# Eload_Gen_3_Power_Module_-_Input_Rev_2.net
KiCad netlist of a schematic drawn in Altium Designer
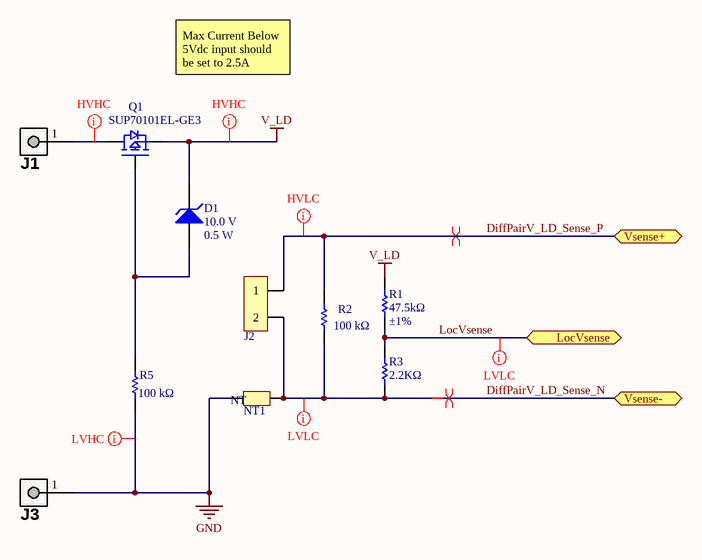
[diagram p0: Eload Gen 3 Power Module - Input Rev 2.SchDoc]

(export (version "E")
  (design (tool "Eeschema 10.0.6"))
  (components
    (comp (ref "D1")
      (value "MMSZ5240BT1G")
      (footprint "SOD123")
      (description "Zener Voltage Regulator, 500 mW, 2-Pin SOD-123, Pb-Free, Tape and Reel")
      (fields (field (name "BREAKDOWN VOLTAGE") "10.0 V") (field (name "POWER RATING") "0.5 W"))
      (libsource (lib "Master JULY2019") (part "Diode, Zener,SOD-123,10V,500mW, MMSZ5240BT1G"))
    )
    (comp (ref "J1")
      (value "wire teminal, lugs, screw, Keystone 8197")
      (footprint "Keystone 8197")
      (fields (field (name "MANUFACTURER PART NUMBER") "8197"))
      (libsource (lib "Master JULY2019") (part "wire teminal, lugs, screw, Keystone 8197"))
    )
    (comp (ref "J2")
      (value "TE Connectivity 282836-2")
      (footprint "TERM BLOCK 2POS SIDE ENTRY 5MM")
      (description "Wire to Board 2 Position 5 mm Pitch 30-16 AWG Euro Style Terminal Block")
      (fields (field (name "MANUFACTURER PART NUMBER") "282836-2"))
      (libsource (lib "Master JULY2019") (part "TERM BLOCK 2POS SIDE ENTRY 5MM, 282836-2"))
    )
    (comp (ref "J3")
      (value "wire teminal, lugs, screw, Keystone 8197")
      (footprint "Keystone 8197")
      (fields (field (name "MANUFACTURER PART NUMBER") "8197"))
      (libsource (lib "Master JULY2019") (part "wire teminal, lugs, screw, Keystone 8197"))
    )
    (comp (ref "NT1")
      (value "Net Tie,0.254mm")
      (footprint "0.254mm Net Tie")
      (libsource (lib "Master Mar2021") (part "Net Tie,0.254mm"))
    )
    (comp (ref "Q1")
      (value "SUP70101EL-GE3")
      (footprint "TO-220 RA")
      (description "MOSFET P-CH 100V 120A TO220AB")
      (fields (field (name "MANUFACTURER") "Vishay Siliconix"))
      (libsource (lib "Master JULY2019") (part "MOSFET,P-Chan,100V,120A,TO220, SUP70101EL-GE3"))
    )
    (comp (ref "R1")
      (value "RK73H2ATTD4752F")
      (footprint "res, 0805, HD")
      (fields
        (field (name "MANUFACTURER") "KOA Speer Electronics, Inc.")
        (field (name "RESISTANCE") "47.5kΩ")
        (field (name "TOLERANCE") "±1%")
      )
      (libsource (lib "Master DEC 2020") (part "Res,0805,47.5KΩ,1%,100ppm,RK73H2ATTD4752F"))
    )
    (comp (ref "R2")
      (value "CRCW0805100KFKEA")
      (footprint "res, 0805, HD")
      (description "100 kOhms ±1% 0.125W, 1/8W Chip Resistor 0805 (2012 Metric) Thick Film")
      (fields (field (name "MANUFACTURER") "Vishay") (field (name "RESISTANCE") "100 kΩ"))
      (libsource (lib "Master Mar2021") (part "Res,0805,100kΩ,1%,100ppm,CRCW0805100KFKEA"))
    )
    (comp (ref "R3")
      (value "CRCW08052K20FKEA")
      (footprint "res, 0805, HD")
      (description "RES SMD 2.2K OHM 1% 1/8W 0805")
      (fields (field (name "RESISTANCE") "2.2KΩ"))
      (libsource (lib "Master DEC 2020") (part "Res,0805,2.2KΩ,±1%,100.0 ppm/°C,150.0 V,CRCW08052K20FKEA"))
    )
    (comp (ref "R5")
      (value "CRCW0805100KFKEA")
      (footprint "res, 0805, HD")
      (description "100 kOhms ±1% 0.125W, 1/8W Chip Resistor 0805 (2012 Metric) Thick Film")
      (fields (field (name "MANUFACTURER") "Vishay") (field (name "RESISTANCE") "100 kΩ"))
      (libsource (lib "Master JULY2019") (part "Res,0805,100kΩ,1%,100ppm,CRCW0805100KFKEA"))
    )
  )
  (nets
    (net (code "1") (name "/DiffPairV_LD_Sense_N") (class "Default")
      (node (ref "J2") (pin "2") (pinfunction "2_2") (pintype "passive"))
      (node (ref "NT1") (pin "2") (pinfunction "2_2") (pintype "passive"))
      (node (ref "R2") (pin "1") (pinfunction "1_1") (pintype "passive"))
      (node (ref "R3") (pin "1") (pinfunction "1_1") (pintype "passive"))
    )
    (net (code "2") (name "/DiffPairV_LD_Sense_P") (class "Default")
      (node (ref "J2") (pin "1") (pinfunction "1_1") (pintype "passive"))
      (node (ref "R2") (pin "2") (pinfunction "2_2") (pintype "passive"))
    )
    (net (code "3") (name "/LocVsense") (class "Default")
      (node (ref "R1") (pin "1") (pinfunction "1_1") (pintype "passive"))
      (node (ref "R3") (pin "2") (pinfunction "2_2") (pintype "passive"))
    )
    (net (code "4") (name "GND") (class "Default")
      (node (ref "J3") (pin "1") (pinfunction "1_1") (pintype "passive"))
      (node (ref "NT1") (pin "1") (pinfunction "1_1") (pintype "passive"))
      (node (ref "R5") (pin "1") (pinfunction "1_1") (pintype "passive"))
    )
    (net (code "5") (name "Net-(D1-A)") (class "Default")
      (node (ref "D1") (pin "2") (pinfunction "A_2") (pintype "passive"))
      (node (ref "Q1") (pin "1") (pinfunction "Gate_1") (pintype "passive"))
      (node (ref "R5") (pin "2") (pinfunction "2_2") (pintype "passive"))
    )
    (net (code "6") (name "Net-(Q1-Drain)") (class "Default")
      (node (ref "J1") (pin "1") (pinfunction "1_1") (pintype "passive"))
      (node (ref "Q1") (pin "2") (pinfunction "Drain_2") (pintype "passive"))
    )
    (net (code "7") (name "V_LD") (class "Default")
      (node (ref "D1") (pin "1") (pinfunction "K_1") (pintype "passive"))
      (node (ref "Q1") (pin "3") (pinfunction "Source_3") (pintype "passive"))
      (node (ref "R1") (pin "2") (pinfunction "2_2") (pintype "passive"))
    )
  )
)
